# Fathom-X.net
KiCad netlist of a schematic drawn in EAGLE
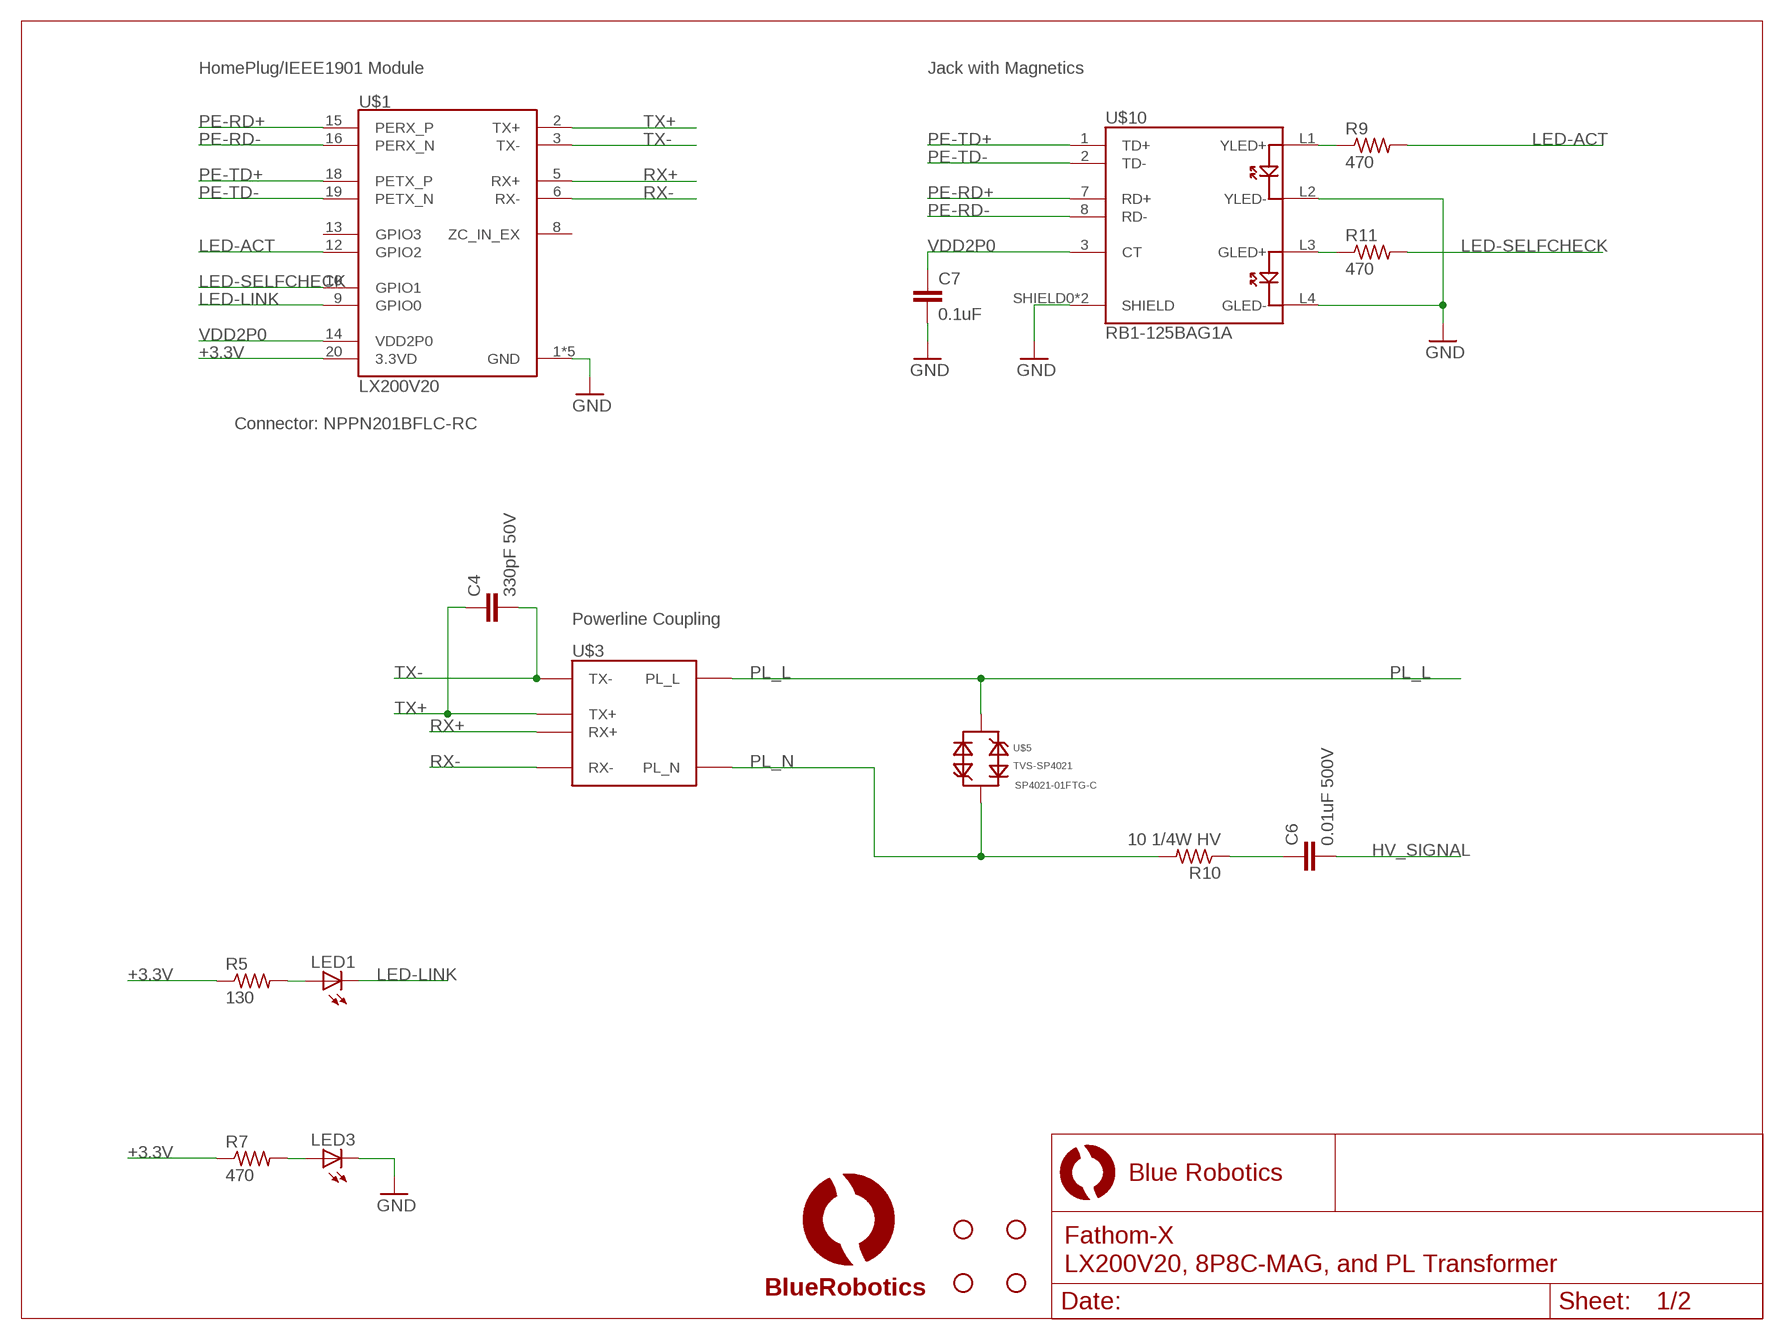
[diagram p0: schematic, sheet 1]
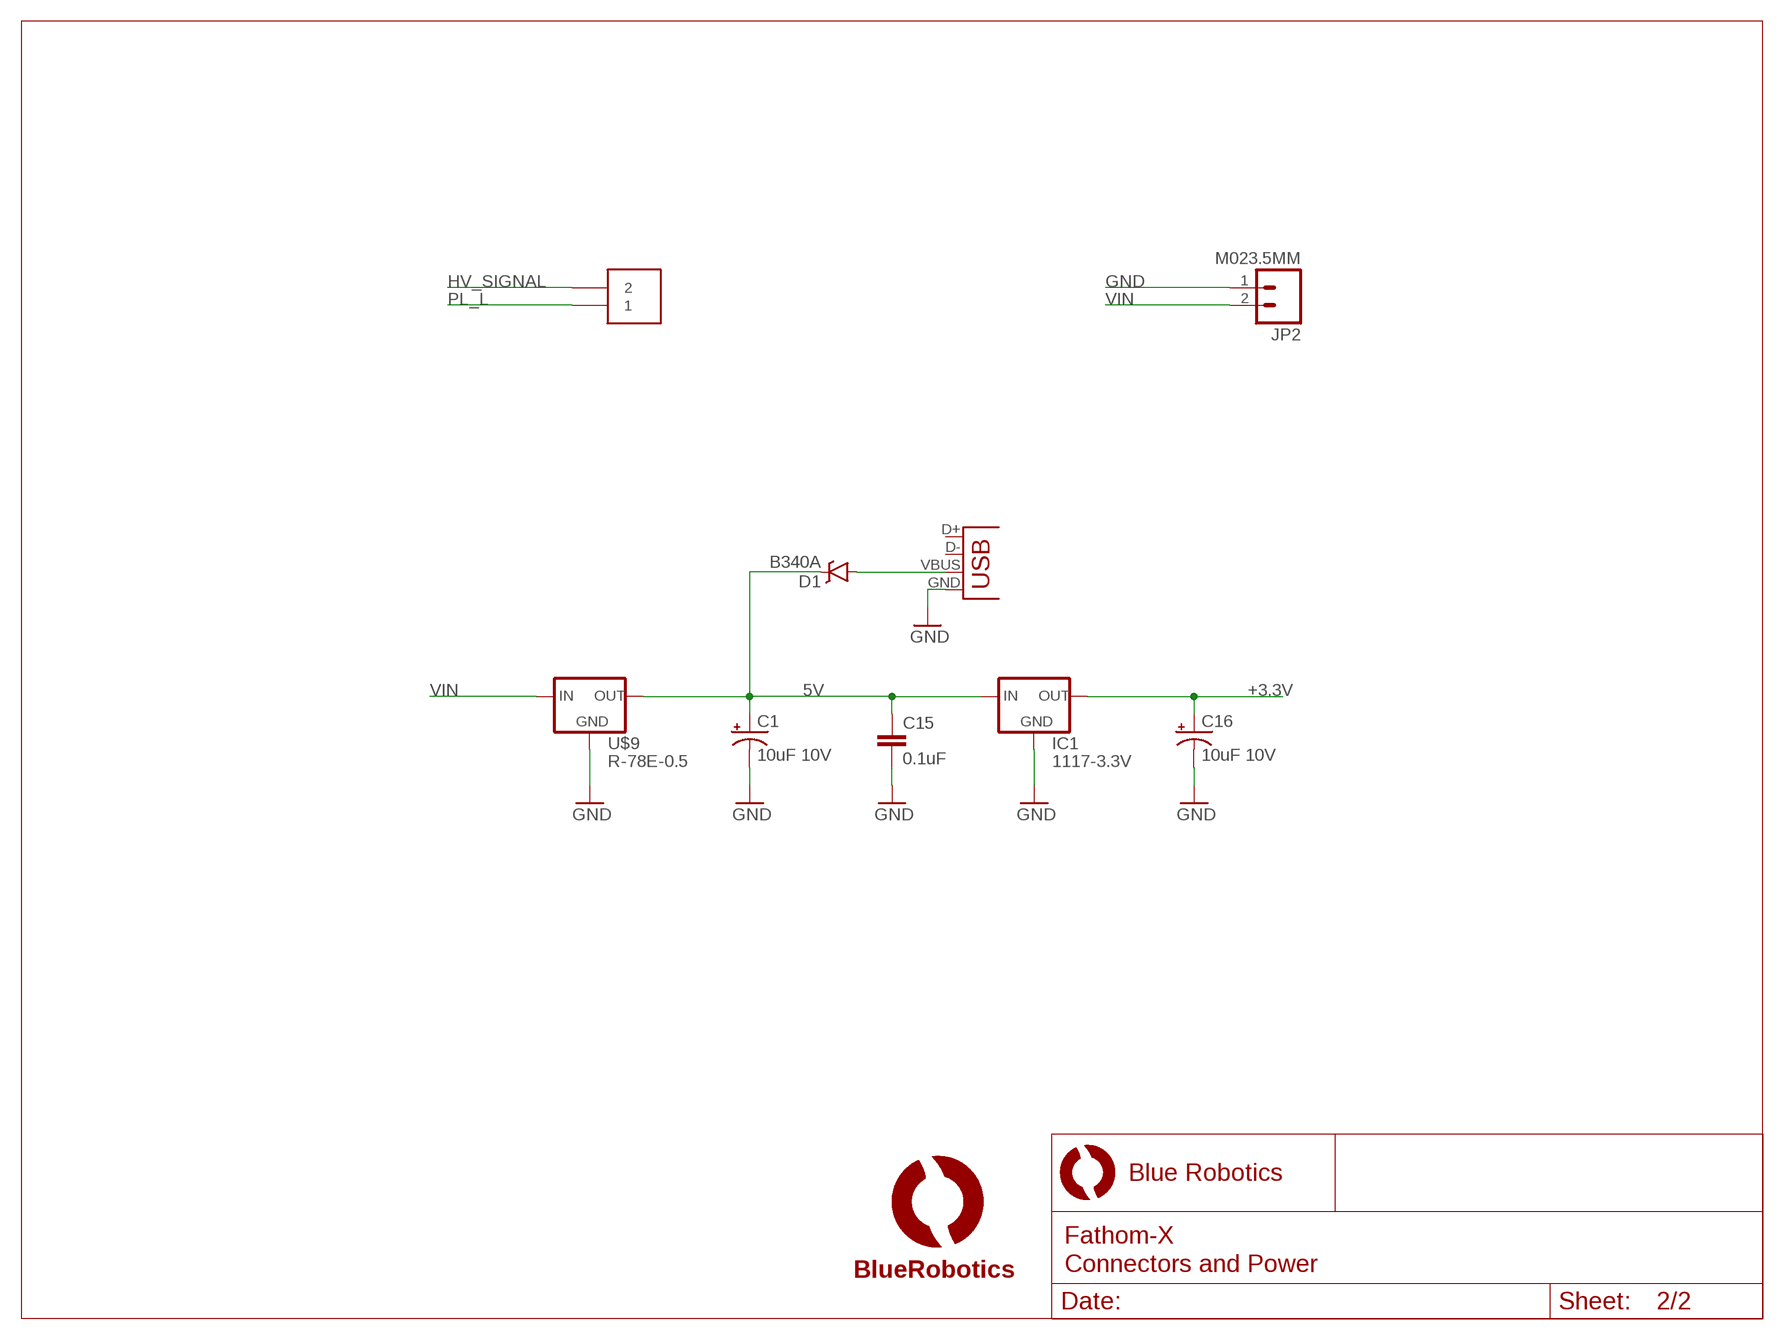
[diagram p1: schematic, sheet 2]

(export (version "E")
  (design (tool "Eeschema 10.0.6"))
  (components
    (comp (ref "C4")
      (value "330pF 50V")
      (footprint "eagle-import:C0805")
      (libsource (lib "eagle-import") (part "C-EUC0805"))
    )
    (comp (ref "C6")
      (value "0.01uF 500V")
      (footprint "eagle-import:C1206")
      (libsource (lib "eagle-import") (part "C-EUC1206"))
    )
    (comp (ref "C7")
      (value "0.1uF")
      (footprint "eagle-import:C0603")
      (libsource (lib "eagle-import") (part "C-EUC0603"))
    )
    (comp (ref "LED1")
      (value "LEDCHIPLED_0603")
      (footprint "eagle-import:CHIPLED_0603")
      (libsource (lib "eagle-import") (part "LEDCHIPLED_0603"))
    )
    (comp (ref "LED3")
      (value "LEDCHIPLED_0603")
      (footprint "eagle-import:CHIPLED_0603")
      (libsource (lib "eagle-import") (part "LEDCHIPLED_0603"))
    )
    (comp (ref "R5")
      (value "130")
      (footprint "eagle-import:R0603")
      (libsource (lib "eagle-import") (part "R-US_R0603"))
    )
    (comp (ref "R7")
      (value "470")
      (footprint "eagle-import:R0603")
      (libsource (lib "eagle-import") (part "R-US_R0603"))
    )
    (comp (ref "R9")
      (value "470")
      (footprint "eagle-import:R0603")
      (libsource (lib "eagle-import") (part "R-US_R0603"))
    )
    (comp (ref "R10")
      (value "10 1/4W HV")
      (footprint "eagle-import:R1206")
      (libsource (lib "eagle-import") (part "R-US_R1206"))
    )
    (comp (ref "R11")
      (value "470")
      (footprint "eagle-import:R0603")
      (libsource (lib "eagle-import") (part "R-US_R0603"))
    )
    (comp (ref "STANDOFF1")
      (value "STAND-OFF")
      (footprint "eagle-import:STAND-OFF")
      (libsource (lib "eagle-import") (part "STAND-OFF"))
    )
    (comp (ref "STANDOFF2")
      (value "STAND-OFF")
      (footprint "eagle-import:STAND-OFF")
      (libsource (lib "eagle-import") (part "STAND-OFF"))
    )
    (comp (ref "STANDOFF3")
      (value "STAND-OFF")
      (footprint "eagle-import:STAND-OFF")
      (libsource (lib "eagle-import") (part "STAND-OFF"))
    )
    (comp (ref "STANDOFF5")
      (value "STAND-OFF")
      (footprint "eagle-import:STAND-OFF")
      (libsource (lib "eagle-import") (part "STAND-OFF"))
    )
    (comp (ref "U$1")
      (value "LX200V20")
      (footprint "eagle-import:LX200V20")
      (libsource (lib "eagle-import") (part "LX200V20"))
    )
    (comp (ref "U$3")
      (value "UT11403S")
      (footprint "eagle-import:UT11403S")
      (libsource (lib "eagle-import") (part "UT11403S"))
    )
    (comp (ref "U$5")
      (value "TVS-SP4021")
      (footprint "eagle-import:SOD323-BIDIRECTIONAL")
      (libsource (lib "eagle-import") (part "TVS-SP4021"))
    )
    (comp (ref "U$6")
      (value "LOGOBR-LOGO-MS-COPPER")
      (footprint "eagle-import:BR-LOGO-MEDIUM-SMALL-COPPER")
      (libsource (lib "eagle-import") (part "LOGOBR-LOGO-MS-COPPER"))
    )
    (comp (ref "U$10")
      (value "RB1-125BAG1A")
      (footprint "eagle-import:RJ45-MAG-WIZNET")
      (libsource (lib "eagle-import") (part "RJ45-MAG"))
    )
    (comp (ref "C1")
      (value "10uF 10V")
      (footprint "eagle-import:EIA3216")
      (libsource (lib "eagle-import") (part "CAP_POL1206"))
    )
    (comp (ref "C15")
      (value "0.1uF")
      (footprint "eagle-import:0603-CAP")
      (libsource (lib "eagle-import") (part "CAP0603-CAP"))
    )
    (comp (ref "C16")
      (value "10uF 10V")
      (footprint "eagle-import:EIA3216")
      (libsource (lib "eagle-import") (part "CAP_POL1206"))
    )
    (comp (ref "D1")
      (value "B340A")
      (footprint "eagle-import:SMA-DIODE")
      (libsource (lib "eagle-import") (part "DIODE-SCHOTTKY-B340A"))
    )
    (comp (ref "IC1")
      (value "1117-3.3V")
      (footprint "eagle-import:SOT223")
      (libsource (lib "eagle-import") (part "VREG-1117-FIXEDSOT223"))
    )
    (comp (ref "JP2")
      (value "M023.5MM")
      (footprint "eagle-import:SCREWTERMINAL-3.5MM-2")
      (libsource (lib "eagle-import") (part "M023.5MM"))
    )
    (comp (ref "JP3")
      (value "USBSMD")
      (footprint "eagle-import:USB-MINIB")
      (libsource (lib "eagle-import") (part "USBSMD"))
    )
    (comp (ref "U$7")
      (value "LOGOFULL-M")
      (footprint "eagle-import:BR-FULL-LOGO-MEDIUM")
      (libsource (lib "eagle-import") (part "LOGOFULL-M"))
    )
    (comp (ref "U$8")
      (value "HEADER-210.16MM")
      (footprint "eagle-import:HEADER-10.16MM-2POS")
      (libsource (lib "eagle-import") (part "HEADER-210.16MM"))
    )
    (comp (ref "U$9")
      (value "R-78E-0.5")
      (footprint "eagle-import:R-78E-0.5")
      (libsource (lib "eagle-import") (part "VREG-R-78E-0.5"))
    )
  )
  (nets
    (net (code "1") (name "+3.3V") (class "Default")
      (node (ref "C16") (pin "A") (pinfunction "+_A") (pintype "passive"))
      (node (ref "IC1") (pin "2") (pinfunction "OUT_2") (pintype "output"))
      (node (ref "R5") (pin "1") (pinfunction "1_1") (pintype "passive"))
      (node (ref "R7") (pin "1") (pinfunction "1_1") (pintype "passive"))
      (node (ref "U$1") (pin "20") (pinfunction "3.3VD_20") (pintype "bidirectional"))
    )
    (net (code "2") (name "5V") (class "Default")
      (node (ref "C1") (pin "A") (pinfunction "+_A") (pintype "passive"))
      (node (ref "C15") (pin "1") (pinfunction "1_1") (pintype "passive"))
      (node (ref "D1") (pin "C") (pinfunction "C_C") (pintype "passive"))
      (node (ref "IC1") (pin "3") (pinfunction "IN_3") (pintype "input"))
      (node (ref "U$9") (pin "VOUT") (pinfunction "OUT_VOUT") (pintype "output"))
    )
    (net (code "3") (name "GND") (class "Default")
      (node (ref "C1") (pin "C") (pinfunction "-_C") (pintype "passive"))
      (node (ref "C15") (pin "2") (pinfunction "2_2") (pintype "passive"))
      (node (ref "C16") (pin "C") (pinfunction "-_C") (pintype "passive"))
      (node (ref "C7") (pin "2") (pinfunction "2_2") (pintype "passive"))
      (node (ref "IC1") (pin "1") (pinfunction "GND_1") (pintype "input"))
      (node (ref "JP2") (pin "1") (pinfunction "1_1") (pintype "passive"))
      (node (ref "JP3") (pin "GND") (pinfunction "GND_GND") (pintype "bidirectional"))
      (node (ref "LED3") (pin "C") (pinfunction "C_C") (pintype "passive"))
      (node (ref "U$1") (pin "1") (pinfunction "GND_1") (pintype "bidirectional"))
      (node (ref "U$1") (pin "11") (pinfunction "GND_11") (pintype "bidirectional"))
      (node (ref "U$1") (pin "17") (pinfunction "GND_17") (pintype "bidirectional"))
      (node (ref "U$1") (pin "4") (pinfunction "GND_4") (pintype "bidirectional"))
      (node (ref "U$1") (pin "7") (pinfunction "GND_7") (pintype "bidirectional"))
      (node (ref "U$10") (pin "L2") (pinfunction "YLED-_L2") (pintype "bidirectional"))
      (node (ref "U$10") (pin "L4") (pinfunction "GLED-_L4") (pintype "bidirectional"))
      (node (ref "U$10") (pin "SHIELD0") (pinfunction "SHIELD_SHIELD0") (pintype "bidirectional"))
      (node (ref "U$10") (pin "SHIELD1") (pinfunction "SHIELD_SHIELD1") (pintype "bidirectional"))
      (node (ref "U$9") (pin "GND") (pinfunction "GND_GND") (pintype "input"))
    )
    (net (code "4") (name "HV_SIGNAL") (class "Default")
      (node (ref "C6") (pin "2") (pinfunction "2_2") (pintype "passive"))
      (node (ref "U$8") (pin "P$2") (pinfunction "2_P$2") (pintype "bidirectional"))
    )
    (net (code "5") (name "LED-ACT") (class "Default")
      (node (ref "R9") (pin "2") (pinfunction "2_2") (pintype "passive"))
      (node (ref "U$1") (pin "12") (pinfunction "GPIO2_12") (pintype "bidirectional"))
    )
    (net (code "6") (name "LED-LINK") (class "Default")
      (node (ref "LED1") (pin "C") (pinfunction "C_C") (pintype "passive"))
      (node (ref "U$1") (pin "9") (pinfunction "GPIO0_9") (pintype "bidirectional"))
    )
    (net (code "7") (name "LED-SELFCHECK") (class "Default")
      (node (ref "R11") (pin "2") (pinfunction "2_2") (pintype "passive"))
      (node (ref "U$1") (pin "10") (pinfunction "GPIO1_10") (pintype "bidirectional"))
    )
    (net (code "8") (name "Net-(C6-Pad1)") (class "Default")
      (node (ref "C6") (pin "1") (pinfunction "1_1") (pintype "passive"))
      (node (ref "R10") (pin "1") (pinfunction "1_1") (pintype "passive"))
    )
    (net (code "9") (name "Net-(D1-PadA)") (class "Default")
      (node (ref "D1") (pin "A") (pinfunction "A_A") (pintype "passive"))
      (node (ref "JP3") (pin "VBUS") (pinfunction "VBUS_VBUS") (pintype "bidirectional"))
    )
    (net (code "10") (name "Net-(LED1-PadA)") (class "Default")
      (node (ref "LED1") (pin "A") (pinfunction "A_A") (pintype "passive"))
      (node (ref "R5") (pin "2") (pinfunction "2_2") (pintype "passive"))
    )
    (net (code "11") (name "Net-(LED3-PadA)") (class "Default")
      (node (ref "LED3") (pin "A") (pinfunction "A_A") (pintype "passive"))
      (node (ref "R7") (pin "2") (pinfunction "2_2") (pintype "passive"))
    )
    (net (code "12") (name "Net-(U$10-GLED+)") (class "Default")
      (node (ref "R11") (pin "1") (pinfunction "1_1") (pintype "passive"))
      (node (ref "U$10") (pin "L3") (pinfunction "GLED+_L3") (pintype "bidirectional"))
    )
    (net (code "13") (name "Net-(U$10-YLED+)") (class "Default")
      (node (ref "R9") (pin "1") (pinfunction "1_1") (pintype "passive"))
      (node (ref "U$10") (pin "L1") (pinfunction "YLED+_L1") (pintype "bidirectional"))
    )
    (net (code "14") (name "PE-RD+") (class "Default")
      (node (ref "U$1") (pin "15") (pinfunction "PERX_P_15") (pintype "bidirectional"))
      (node (ref "U$10") (pin "7") (pinfunction "RD+_7") (pintype "bidirectional"))
    )
    (net (code "15") (name "PE-RD-") (class "Default")
      (node (ref "U$1") (pin "16") (pinfunction "PERX_N_16") (pintype "bidirectional"))
      (node (ref "U$10") (pin "8") (pinfunction "RD-_8") (pintype "bidirectional"))
    )
    (net (code "16") (name "PE-TD+") (class "Default")
      (node (ref "U$1") (pin "18") (pinfunction "PETX_P_18") (pintype "bidirectional"))
      (node (ref "U$10") (pin "1") (pinfunction "TD+_1") (pintype "bidirectional"))
    )
    (net (code "17") (name "PE-TD-") (class "Default")
      (node (ref "U$1") (pin "19") (pinfunction "PETX_N_19") (pintype "bidirectional"))
      (node (ref "U$10") (pin "2") (pinfunction "TD-_2") (pintype "bidirectional"))
    )
    (net (code "18") (name "PL_L") (class "Default")
      (node (ref "U$3") (pin "PL_L") (pinfunction "PL_L_PL_L") (pintype "bidirectional"))
      (node (ref "U$5") (pin "2") (pinfunction "P$2_2") (pintype "bidirectional"))
      (node (ref "U$8") (pin "P$1") (pinfunction "1_P$1") (pintype "bidirectional"))
    )
    (net (code "19") (name "PL_N") (class "Default")
      (node (ref "R10") (pin "2") (pinfunction "2_2") (pintype "passive"))
      (node (ref "U$3") (pin "PL_N") (pinfunction "PL_N_PL_N") (pintype "bidirectional"))
      (node (ref "U$5") (pin "1") (pinfunction "P$1_1") (pintype "bidirectional"))
    )
    (net (code "20") (name "RX+") (class "Default")
      (node (ref "U$1") (pin "5") (pinfunction "RX+_5") (pintype "bidirectional"))
      (node (ref "U$3") (pin "RX+") (pinfunction "RX+_RX+") (pintype "bidirectional"))
    )
    (net (code "21") (name "RX-") (class "Default")
      (node (ref "U$1") (pin "6") (pinfunction "RX-_6") (pintype "bidirectional"))
      (node (ref "U$3") (pin "RX-") (pinfunction "RX-_RX-") (pintype "bidirectional"))
    )
    (net (code "22") (name "TX+") (class "Default")
      (node (ref "C4") (pin "1") (pinfunction "1_1") (pintype "passive"))
      (node (ref "U$1") (pin "2") (pinfunction "TX+_2") (pintype "bidirectional"))
      (node (ref "U$3") (pin "TX+") (pinfunction "TX+_TX+") (pintype "bidirectional"))
    )
    (net (code "23") (name "TX-") (class "Default")
      (node (ref "C4") (pin "2") (pinfunction "2_2") (pintype "passive"))
      (node (ref "U$1") (pin "3") (pinfunction "TX-_3") (pintype "bidirectional"))
      (node (ref "U$3") (pin "TX-") (pinfunction "TX-_TX-") (pintype "bidirectional"))
    )
    (net (code "24") (name "VDD2P0") (class "Default")
      (node (ref "C7") (pin "1") (pinfunction "1_1") (pintype "passive"))
      (node (ref "U$1") (pin "14") (pinfunction "VDD2P0_14") (pintype "bidirectional"))
      (node (ref "U$10") (pin "3") (pinfunction "CT_3") (pintype "bidirectional"))
    )
    (net (code "25") (name "VIN") (class "Default")
      (node (ref "JP2") (pin "2") (pinfunction "2_2") (pintype "passive"))
      (node (ref "U$9") (pin "VIN") (pinfunction "IN_VIN") (pintype "input"))
    )
    (net (code "26") (name "unconnected-(JP3-PadD+)") (class "Default")
      (node (ref "JP3") (pin "D+") (pinfunction "D+_D+") (pintype "bidirectional"))
    )
    (net (code "27") (name "unconnected-(JP3-PadD-)") (class "Default")
      (node (ref "JP3") (pin "D-") (pinfunction "D-_D-") (pintype "bidirectional"))
    )
    (net (code "28") (name "unconnected-(U$1-GPIO3-Pad13)") (class "Default")
      (node (ref "U$1") (pin "13") (pinfunction "GPIO3_13") (pintype "bidirectional"))
    )
    (net (code "29") (name "unconnected-(U$1-ZC_IN_EX-Pad8)") (class "Default")
      (node (ref "U$1") (pin "8") (pinfunction "ZC_IN_EX_8") (pintype "bidirectional"))
    )
  )
)
